# BreakBeamEmitter.net
KiCad netlist of a schematic drawn in EAGLE
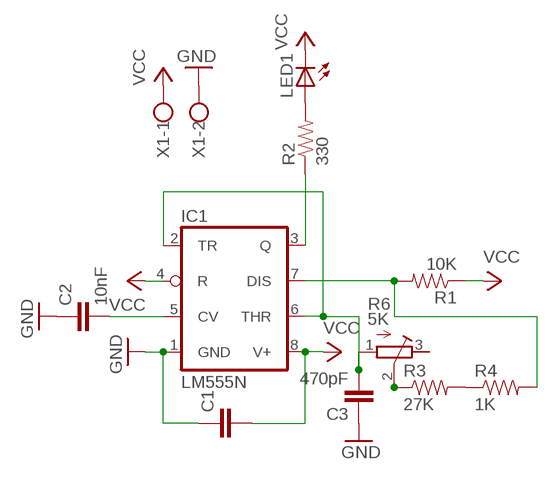
[diagram p0: schematic, sheet 1]

(export (version "E")
  (design (tool "Eeschema 10.0.6"))
  (components
    (comp (ref "C1")
      (value "CAPPTH1")
      (footprint "eagle-import:CAP-PTH-5MM")
      (libsource (lib "eagle-import") (part "CAPPTH1"))
    )
    (comp (ref "C2")
      (value "10nF")
      (footprint "eagle-import:CAP-PTH-5MM")
      (libsource (lib "eagle-import") (part "CAPPTH1"))
    )
    (comp (ref "C3")
      (value "470pF")
      (footprint "eagle-import:CAP-PTH-5MM")
      (libsource (lib "eagle-import") (part "CAPPTH1"))
    )
    (comp (ref "IC1")
      (value "LM555N")
      (footprint "eagle-import:DIL08-ROUND")
      (libsource (lib "eagle-import") (part "555NLM"))
    )
    (comp (ref "LED1")
      (value "LED5MM")
      (footprint "eagle-import:LED5MM")
      (libsource (lib "eagle-import") (part "LED5MM"))
    )
    (comp (ref "R1")
      (value "10K")
      (footprint "eagle-import:AXIAL-0.3")
      (libsource (lib "eagle-import") (part "RESISTORAXIAL-0.3"))
    )
    (comp (ref "R2")
      (value "330")
      (footprint "eagle-import:AXIAL-0.3")
      (libsource (lib "eagle-import") (part "RESISTORAXIAL-0.3"))
    )
    (comp (ref "R3")
      (value "27K")
      (footprint "eagle-import:AXIAL-0.3")
      (libsource (lib "eagle-import") (part "RESISTORAXIAL-0.3"))
    )
    (comp (ref "R4")
      (value "1K")
      (footprint "eagle-import:AXIAL-0.3")
      (libsource (lib "eagle-import") (part "RESISTORAXIAL-0.3"))
    )
    (comp (ref "R6")
      (value "5K")
      (footprint "eagle-import:RTRIM64Y")
      (libsource (lib "eagle-import") (part "R-TRIMM64Y"))
    )
    (comp (ref "X1")
      (value "W237-102")
      (footprint "eagle-import:W237-102")
      (fields (field (name "MPN") "237-102"))
      (libsource (lib "eagle-import") (part "W237-102"))
    )
  )
  (nets
    (net (code "1") (name "GND") (class "Default")
      (node (ref "C1") (pin "1") (pinfunction "1_1") (pintype "passive"))
      (node (ref "C2") (pin "1") (pinfunction "1_1") (pintype "passive"))
      (node (ref "C3") (pin "1") (pinfunction "1_1") (pintype "passive"))
      (node (ref "IC1") (pin "1") (pinfunction "GND_1") (pintype "power_in"))
      (node (ref "X1") (pin "2") (pinfunction "KL_2") (pintype "passive"))
    )
    (net (code "2") (name "Net-(IC1-CV)") (class "Default")
      (node (ref "C2") (pin "2") (pinfunction "2_2") (pintype "passive"))
      (node (ref "IC1") (pin "5") (pinfunction "CV_5") (pintype "input"))
    )
    (net (code "3") (name "Net-(IC1-DIS)") (class "Default")
      (node (ref "IC1") (pin "7") (pinfunction "DIS_7") (pintype "input"))
      (node (ref "R1") (pin "P$2") (pinfunction "2_P$2") (pintype "passive"))
      (node (ref "R4") (pin "P$2") (pinfunction "2_P$2") (pintype "passive"))
    )
    (net (code "4") (name "Net-(IC1-Q)") (class "Default")
      (node (ref "IC1") (pin "3") (pinfunction "Q_3") (pintype "output"))
      (node (ref "R2") (pin "P$1") (pinfunction "1_P$1") (pintype "passive"))
    )
    (net (code "5") (name "Net-(IC1-THR)") (class "Default")
      (node (ref "C3") (pin "2") (pinfunction "2_2") (pintype "passive"))
      (node (ref "IC1") (pin "2") (pinfunction "TR_2") (pintype "input"))
      (node (ref "IC1") (pin "6") (pinfunction "THR_6") (pintype "input"))
      (node (ref "R6") (pin "1") (pinfunction "E_1") (pintype "passive"))
    )
    (net (code "6") (name "Net-(R2-2)") (class "Default")
      (node (ref "LED1") (pin "A") (pinfunction "A_A") (pintype "passive"))
      (node (ref "R2") (pin "P$2") (pinfunction "2_P$2") (pintype "passive"))
    )
    (net (code "7") (name "Net-(R3-1)") (class "Default")
      (node (ref "R3") (pin "P$1") (pinfunction "1_P$1") (pintype "passive"))
      (node (ref "R6") (pin "2") (pinfunction "S_2") (pintype "passive"))
    )
    (net (code "8") (name "Net-(R3-2)") (class "Default")
      (node (ref "R3") (pin "P$2") (pinfunction "2_P$2") (pintype "passive"))
      (node (ref "R4") (pin "P$1") (pinfunction "1_P$1") (pintype "passive"))
    )
    (net (code "9") (name "VCC") (class "Default")
      (node (ref "C1") (pin "2") (pinfunction "2_2") (pintype "passive"))
      (node (ref "IC1") (pin "4") (pinfunction "R_4") (pintype "input"))
      (node (ref "IC1") (pin "8") (pinfunction "V+_8") (pintype "power_in"))
      (node (ref "LED1") (pin "K") (pinfunction "C_K") (pintype "passive"))
      (node (ref "R1") (pin "P$1") (pinfunction "1_P$1") (pintype "passive"))
      (node (ref "X1") (pin "1") (pinfunction "KL_1") (pintype "passive"))
    )
    (net (code "10") (name "unconnected-(R6-A-Pad3)") (class "Default")
      (node (ref "R6") (pin "3") (pinfunction "A_3") (pintype "passive"))
    )
  )
)
